# OMSI_TABLE12_v1.net
KiCad netlist of a schematic drawn in EAGLE
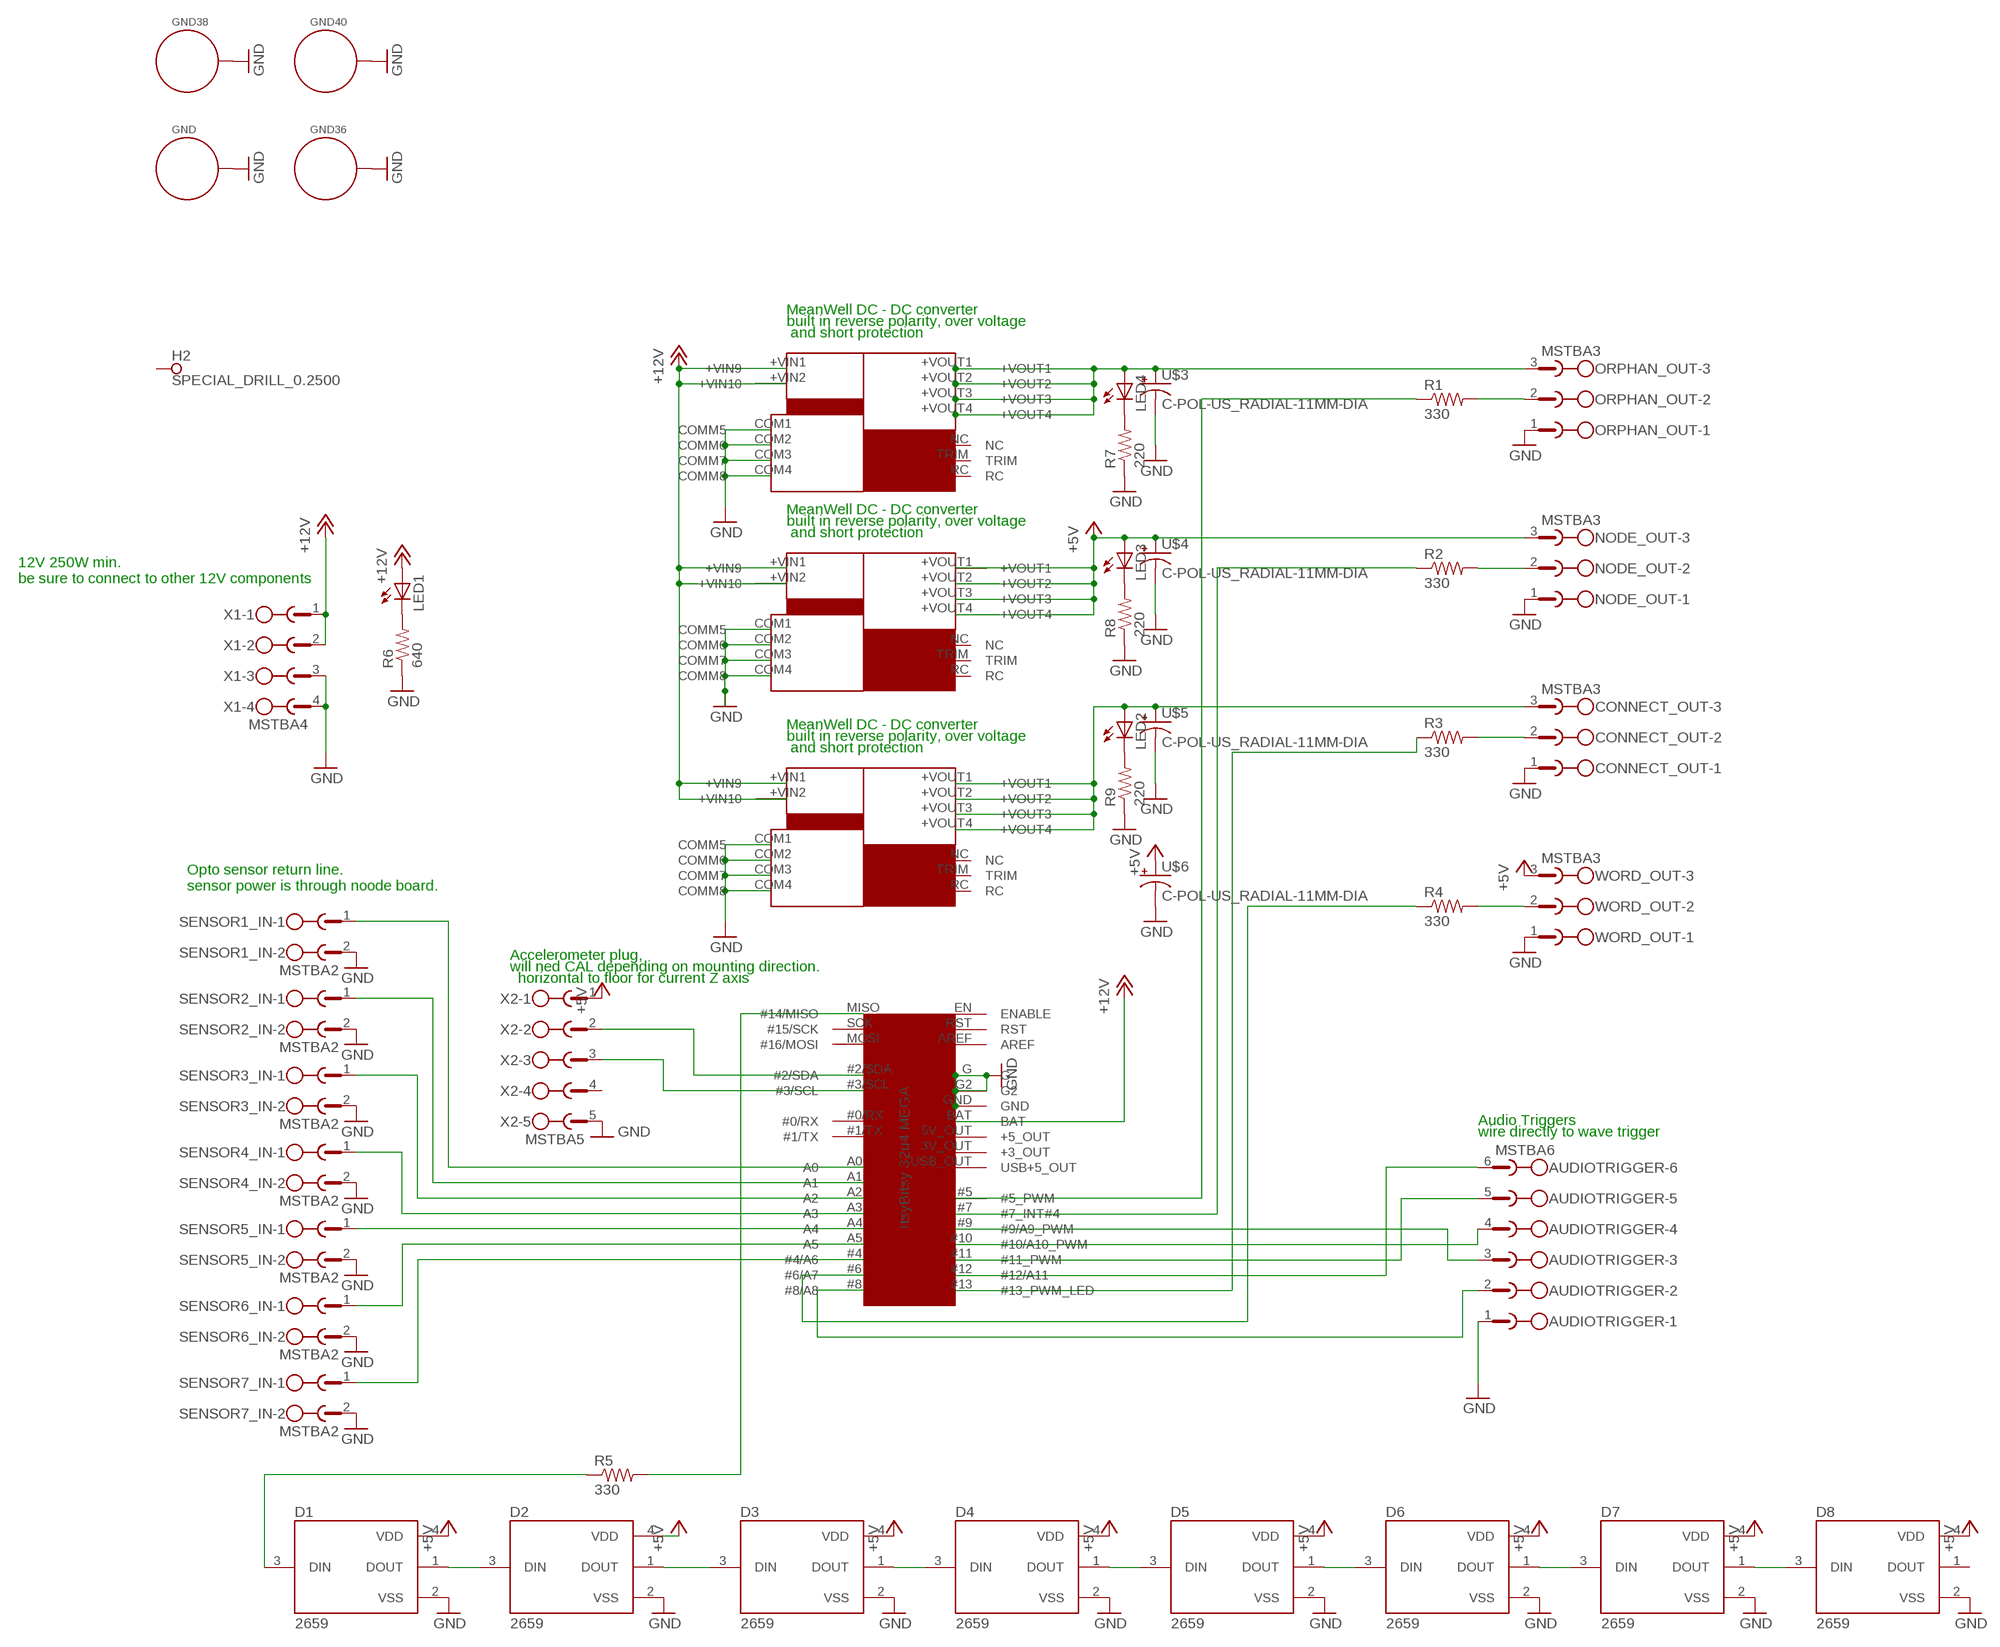
[diagram p0: schematic, sheet 1]

(export (version "E")
  (design (tool "Eeschema 10.0.6"))
  (components
    (comp (ref "AUDIOTRIGGER")
      (value "MSTBA6")
      (footprint "eagle-import:MSTBA6")
      (fields (field (name "MF") "FARNELL") (field (name "MPN") "1757284"))
      (libsource (lib "eagle-import") (part "MSTBA6"))
    )
    (comp (ref "CONNECT_OUT")
      (value "MSTBA3")
      (footprint "eagle-import:MSTBA3")
      (fields (field (name "MF") "FARNELL") (field (name "MPN") "1757255"))
      (libsource (lib "eagle-import") (part "MSTBA3"))
    )
    (comp (ref "D1")
      (value "2659")
      (footprint "eagle-import:2659")
      (fields (field (name "MF") "Adafruit Industries"))
      (libsource (lib "eagle-import") (part "2659"))
    )
    (comp (ref "D2")
      (value "2659")
      (footprint "eagle-import:2659")
      (fields (field (name "MF") "Adafruit Industries"))
      (libsource (lib "eagle-import") (part "2659"))
    )
    (comp (ref "D3")
      (value "2659")
      (footprint "eagle-import:2659")
      (fields (field (name "MF") "Adafruit Industries"))
      (libsource (lib "eagle-import") (part "2659"))
    )
    (comp (ref "D4")
      (value "2659")
      (footprint "eagle-import:2659")
      (fields (field (name "MF") "Adafruit Industries"))
      (libsource (lib "eagle-import") (part "2659"))
    )
    (comp (ref "D5")
      (value "2659")
      (footprint "eagle-import:2659")
      (fields (field (name "MF") "Adafruit Industries"))
      (libsource (lib "eagle-import") (part "2659"))
    )
    (comp (ref "D6")
      (value "2659")
      (footprint "eagle-import:2659")
      (fields (field (name "MF") "Adafruit Industries"))
      (libsource (lib "eagle-import") (part "2659"))
    )
    (comp (ref "D7")
      (value "2659")
      (footprint "eagle-import:2659")
      (fields (field (name "MF") "Adafruit Industries"))
      (libsource (lib "eagle-import") (part "2659"))
    )
    (comp (ref "D8")
      (value "2659")
      (footprint "eagle-import:2659")
      (fields (field (name "MF") "Adafruit Industries"))
      (libsource (lib "eagle-import") (part "2659"))
    )
    (comp (ref "GND")
      (value "STANDOFF_ELECTRICAL5-32")
      (footprint "eagle-import:STANDOFF_ELECTRICAL_5_32")
      (libsource (lib "eagle-import") (part "STANDOFF_ELECTRICAL5-32"))
    )
    (comp (ref "GND36")
      (value "STANDOFF_ELECTRICAL5-32")
      (footprint "eagle-import:STANDOFF_ELECTRICAL_5_32")
      (libsource (lib "eagle-import") (part "STANDOFF_ELECTRICAL5-32"))
    )
    (comp (ref "GND38")
      (value "STANDOFF_ELECTRICAL5-32")
      (footprint "eagle-import:STANDOFF_ELECTRICAL_5_32")
      (libsource (lib "eagle-import") (part "STANDOFF_ELECTRICAL5-32"))
    )
    (comp (ref "GND40")
      (value "STANDOFF_ELECTRICAL5-32")
      (footprint "eagle-import:STANDOFF_ELECTRICAL_5_32")
      (libsource (lib "eagle-import") (part "STANDOFF_ELECTRICAL5-32"))
    )
    (comp (ref "H2")
      (value "SPECIAL_DRILL_0.2500")
      (footprint "eagle-import:PAD_0.2500")
      (libsource (lib "eagle-import") (part "SPECIAL_DRILL_0.2500"))
    )
    (comp (ref "LED1")
      (value "LEDCHIPLED_1206")
      (footprint "eagle-import:CHIPLED_1206")
      (libsource (lib "eagle-import") (part "LEDCHIPLED_1206"))
    )
    (comp (ref "LED2")
      (value "LEDCHIPLED_1206")
      (footprint "eagle-import:CHIPLED_1206")
      (libsource (lib "eagle-import") (part "LEDCHIPLED_1206"))
    )
    (comp (ref "LED3")
      (value "LEDCHIPLED_1206")
      (footprint "eagle-import:CHIPLED_1206")
      (libsource (lib "eagle-import") (part "LEDCHIPLED_1206"))
    )
    (comp (ref "LED4")
      (value "LEDCHIPLED_1206")
      (footprint "eagle-import:CHIPLED_1206")
      (libsource (lib "eagle-import") (part "LEDCHIPLED_1206"))
    )
    (comp (ref "MEANWELL_NID100_1")
      (value "MEANWELL_NID100")
      (footprint "eagle-import:MEANWELL_NID100")
      (libsource (lib "eagle-import") (part "MEANWELL_NID100"))
    )
    (comp (ref "MEANWELL_NID100_2")
      (value "MEANWELL_NID100")
      (footprint "eagle-import:MEANWELL_NID100")
      (libsource (lib "eagle-import") (part "MEANWELL_NID100"))
    )
    (comp (ref "MEANWELL_NID100_3")
      (value "MEANWELL_NID100")
      (footprint "eagle-import:MEANWELL_NID100")
      (libsource (lib "eagle-import") (part "MEANWELL_NID100"))
    )
    (comp (ref "NODE_OUT")
      (value "MSTBA3")
      (footprint "eagle-import:MSTBA3")
      (fields (field (name "MF") "FARNELL") (field (name "MPN") "1757255"))
      (libsource (lib "eagle-import") (part "MSTBA3"))
    )
    (comp (ref "ORPHAN_OUT")
      (value "MSTBA3")
      (footprint "eagle-import:MSTBA3")
      (fields (field (name "MF") "FARNELL") (field (name "MPN") "1757255"))
      (libsource (lib "eagle-import") (part "MSTBA3"))
    )
    (comp (ref "R1")
      (value "330")
      (footprint "eagle-import:RESAD1176W63L850D250B")
      (libsource (lib "eagle-import") (part "R-USAXIAL-11.7MM-PITCH_"))
    )
    (comp (ref "R2")
      (value "330")
      (footprint "eagle-import:RESAD1176W63L850D250B")
      (libsource (lib "eagle-import") (part "R-USAXIAL-11.7MM-PITCH_"))
    )
    (comp (ref "R3")
      (value "330")
      (footprint "eagle-import:RESAD1176W63L850D250B")
      (libsource (lib "eagle-import") (part "R-USAXIAL-11.7MM-PITCH_"))
    )
    (comp (ref "R4")
      (value "330")
      (footprint "eagle-import:RESAD1176W63L850D250B")
      (libsource (lib "eagle-import") (part "R-USAXIAL-11.7MM-PITCH_"))
    )
    (comp (ref "R5")
      (value "330")
      (footprint "eagle-import:RESAD1176W63L850D250B")
      (libsource (lib "eagle-import") (part "R-USAXIAL-11.7MM-PITCH_"))
    )
    (comp (ref "R6")
      (value "640")
      (footprint "eagle-import:R0805")
      (libsource (lib "eagle-import") (part "adafruit_420_R-US_R0805"))
    )
    (comp (ref "R7")
      (value "220")
      (footprint "eagle-import:R0805")
      (libsource (lib "eagle-import") (part "R-US_R0805"))
    )
    (comp (ref "R8")
      (value "220")
      (footprint "eagle-import:R0805")
      (libsource (lib "eagle-import") (part "R-US_R0805"))
    )
    (comp (ref "R9")
      (value "220")
      (footprint "eagle-import:R0805")
      (libsource (lib "eagle-import") (part "R-US_R0805"))
    )
    (comp (ref "SENSOR1_IN")
      (value "MSTBA2")
      (footprint "eagle-import:MSTBA2")
      (fields (field (name "MF") "FARNELL") (field (name "MPN") "1757242"))
      (libsource (lib "eagle-import") (part "MSTBA2"))
    )
    (comp (ref "SENSOR2_IN")
      (value "MSTBA2")
      (footprint "eagle-import:MSTBA2")
      (fields (field (name "MF") "FARNELL") (field (name "MPN") "1757242"))
      (libsource (lib "eagle-import") (part "MSTBA2"))
    )
    (comp (ref "SENSOR3_IN")
      (value "MSTBA2")
      (footprint "eagle-import:MSTBA2")
      (fields (field (name "MF") "FARNELL") (field (name "MPN") "1757242"))
      (libsource (lib "eagle-import") (part "MSTBA2"))
    )
    (comp (ref "SENSOR4_IN")
      (value "MSTBA2")
      (footprint "eagle-import:MSTBA2")
      (fields (field (name "MF") "FARNELL") (field (name "MPN") "1757242"))
      (libsource (lib "eagle-import") (part "MSTBA2"))
    )
    (comp (ref "SENSOR5_IN")
      (value "MSTBA2")
      (footprint "eagle-import:MSTBA2")
      (fields (field (name "MF") "FARNELL") (field (name "MPN") "1757242"))
      (libsource (lib "eagle-import") (part "MSTBA2"))
    )
    (comp (ref "SENSOR6_IN")
      (value "MSTBA2")
      (footprint "eagle-import:MSTBA2")
      (fields (field (name "MF") "FARNELL") (field (name "MPN") "1757242"))
      (libsource (lib "eagle-import") (part "MSTBA2"))
    )
    (comp (ref "SENSOR7_IN")
      (value "MSTBA2")
      (footprint "eagle-import:MSTBA2")
      (fields (field (name "MF") "FARNELL") (field (name "MPN") "1757242"))
      (libsource (lib "eagle-import") (part "MSTBA2"))
    )
    (comp (ref "U$1")
      (value "ITSYBITSY_32U4")
      (footprint "eagle-import:ITSYBITSY_32U4")
      (libsource (lib "eagle-import") (part "ITSYBITSY_32U4"))
    )
    (comp (ref "U$3")
      (value "C-POL-US_RADIAL-11MM-DIA")
      (footprint "eagle-import:CAPPRD508W65D1000H1100B")
      (libsource (lib "eagle-import") (part "C-POL-USRADIAL-11MM-DIA_"))
    )
    (comp (ref "U$4")
      (value "C-POL-US_RADIAL-11MM-DIA")
      (footprint "eagle-import:CAPPRD508W65D1000H1100B")
      (libsource (lib "eagle-import") (part "C-POL-USRADIAL-11MM-DIA_"))
    )
    (comp (ref "U$5")
      (value "C-POL-US_RADIAL-11MM-DIA")
      (footprint "eagle-import:CAPPRD508W65D1000H1100B")
      (libsource (lib "eagle-import") (part "C-POL-USRADIAL-11MM-DIA_"))
    )
    (comp (ref "U$6")
      (value "C-POL-US_RADIAL-11MM-DIA")
      (footprint "eagle-import:CAPPRD508W65D1000H1100B")
      (libsource (lib "eagle-import") (part "C-POL-USRADIAL-11MM-DIA_"))
    )
    (comp (ref "WORD_OUT")
      (value "MSTBA3")
      (footprint "eagle-import:MSTBA3")
      (fields (field (name "MF") "FARNELL") (field (name "MPN") "1757255"))
      (libsource (lib "eagle-import") (part "MSTBA3"))
    )
    (comp (ref "X1")
      (value "MSTBA4")
      (footprint "eagle-import:MSTBA4")
      (fields (field (name "MF") "FARNELL") (field (name "MPN") "1757268"))
      (libsource (lib "eagle-import") (part "MSTBA4"))
    )
    (comp (ref "X2")
      (value "MSTBA5")
      (footprint "eagle-import:MSTBA5")
      (fields (field (name "MPN") "1757271"))
      (libsource (lib "eagle-import") (part "MSTBA5"))
    )
  )
  (nets
    (net (code "1") (name "+5V") (class "Default")
      (node (ref "D1") (pin "4") (pinfunction "VDD_4") (pintype "power_in"))
      (node (ref "D2") (pin "4") (pinfunction "VDD_4") (pintype "power_in"))
      (node (ref "D3") (pin "4") (pinfunction "VDD_4") (pintype "power_in"))
      (node (ref "D4") (pin "4") (pinfunction "VDD_4") (pintype "power_in"))
      (node (ref "D5") (pin "4") (pinfunction "VDD_4") (pintype "power_in"))
      (node (ref "D6") (pin "4") (pinfunction "VDD_4") (pintype "power_in"))
      (node (ref "D7") (pin "4") (pinfunction "VDD_4") (pintype "power_in"))
      (node (ref "D8") (pin "4") (pinfunction "VDD_4") (pintype "power_in"))
      (node (ref "LED3") (pin "A") (pinfunction "A_A") (pintype "passive"))
      (node (ref "MEANWELL_NID100_3") (pin "+VOUT1") (pinfunction "+VOUT1_+VOUT1") (pintype "power_in"))
      (node (ref "MEANWELL_NID100_3") (pin "+VOUT2") (pinfunction "+VOUT2_+VOUT2") (pintype "power_in"))
      (node (ref "MEANWELL_NID100_3") (pin "+VOUT3") (pinfunction "+VOUT3_+VOUT3") (pintype "power_in"))
      (node (ref "MEANWELL_NID100_3") (pin "+VOUT4") (pinfunction "+VOUT4_+VOUT4") (pintype "power_in"))
      (node (ref "NODE_OUT") (pin "3") (pinfunction "1_3") (pintype "passive"))
      (node (ref "U$4") (pin "1") (pinfunction "+_1") (pintype "passive"))
      (node (ref "U$6") (pin "1") (pinfunction "+_1") (pintype "passive"))
      (node (ref "WORD_OUT") (pin "3") (pinfunction "1_3") (pintype "passive"))
      (node (ref "X2") (pin "1") (pinfunction "1_1") (pintype "passive"))
    )
    (net (code "2") (name "+12V") (class "Default")
      (node (ref "LED1") (pin "A") (pinfunction "A_A") (pintype "passive"))
      (node (ref "MEANWELL_NID100_1") (pin "+VIN1") (pinfunction "+VIN9_+VIN1") (pintype "power_in"))
      (node (ref "MEANWELL_NID100_1") (pin "+VIN2") (pinfunction "+VIN10_+VIN2") (pintype "power_in"))
      (node (ref "MEANWELL_NID100_2") (pin "+VIN1") (pinfunction "+VIN9_+VIN1") (pintype "power_in"))
      (node (ref "MEANWELL_NID100_2") (pin "+VIN2") (pinfunction "+VIN10_+VIN2") (pintype "power_in"))
      (node (ref "MEANWELL_NID100_3") (pin "+VIN1") (pinfunction "+VIN9_+VIN1") (pintype "power_in"))
      (node (ref "MEANWELL_NID100_3") (pin "+VIN2") (pinfunction "+VIN10_+VIN2") (pintype "power_in"))
      (node (ref "U$1") (pin "BAT") (pinfunction "BAT_BAT") (pintype "power_in"))
      (node (ref "X1") (pin "1") (pinfunction "1_1") (pintype "passive"))
      (node (ref "X1") (pin "2") (pinfunction "1_2") (pintype "passive"))
    )
    (net (code "3") (name "/+3_OUT") (class "Default")
      (node (ref "U$1") (pin "3V_OUT") (pinfunction "+3_OUT_3V_OUT") (pintype "power_in"))
    )
    (net (code "4") (name "/+5_OUT") (class "Default")
      (node (ref "U$1") (pin "5V_OUT") (pinfunction "+5_OUT_5V_OUT") (pintype "power_in"))
    )
    (net (code "5") (name "/AREF") (class "Default")
      (node (ref "U$1") (pin "AREF") (pinfunction "AREF_AREF") (pintype "power_in"))
    )
    (net (code "6") (name "/RST") (class "Default")
      (node (ref "U$1") (pin "RST") (pinfunction "RST_RST") (pintype "power_in"))
    )
    (net (code "7") (name "/USB+5_OUT") (class "Default")
      (node (ref "U$1") (pin "USB_OUT") (pinfunction "USB+5_OUT_USB_OUT") (pintype "power_in"))
    )
    (net (code "8") (name "GND") (class "Default")
      (node (ref "AUDIOTRIGGER") (pin "1") (pinfunction "1_1") (pintype "passive"))
      (node (ref "CONNECT_OUT") (pin "1") (pinfunction "1_1") (pintype "passive"))
      (node (ref "D1") (pin "2") (pinfunction "VSS_2") (pintype "power_in"))
      (node (ref "D2") (pin "2") (pinfunction "VSS_2") (pintype "power_in"))
      (node (ref "D3") (pin "2") (pinfunction "VSS_2") (pintype "power_in"))
      (node (ref "D4") (pin "2") (pinfunction "VSS_2") (pintype "power_in"))
      (node (ref "D5") (pin "2") (pinfunction "VSS_2") (pintype "power_in"))
      (node (ref "D6") (pin "2") (pinfunction "VSS_2") (pintype "power_in"))
      (node (ref "D7") (pin "2") (pinfunction "VSS_2") (pintype "power_in"))
      (node (ref "D8") (pin "2") (pinfunction "VSS_2") (pintype "power_in"))
      (node (ref "GND") (pin "P1") (pinfunction "P$1_P1") (pintype "bidirectional"))
      (node (ref "GND36") (pin "P1") (pinfunction "P$1_P1") (pintype "bidirectional"))
      (node (ref "GND38") (pin "P1") (pinfunction "P$1_P1") (pintype "bidirectional"))
      (node (ref "GND40") (pin "P1") (pinfunction "P$1_P1") (pintype "bidirectional"))
      (node (ref "MEANWELL_NID100_1") (pin "COM1") (pinfunction "COMM5_COM1") (pintype "power_in"))
      (node (ref "MEANWELL_NID100_1") (pin "COM2") (pinfunction "COMM6_COM2") (pintype "power_in"))
      (node (ref "MEANWELL_NID100_1") (pin "COM3") (pinfunction "COMM7_COM3") (pintype "power_in"))
      (node (ref "MEANWELL_NID100_1") (pin "COM4") (pinfunction "COMM8_COM4") (pintype "power_in"))
      (node (ref "MEANWELL_NID100_2") (pin "COM1") (pinfunction "COMM5_COM1") (pintype "power_in"))
      (node (ref "MEANWELL_NID100_2") (pin "COM2") (pinfunction "COMM6_COM2") (pintype "power_in"))
      (node (ref "MEANWELL_NID100_2") (pin "COM3") (pinfunction "COMM7_COM3") (pintype "power_in"))
      (node (ref "MEANWELL_NID100_2") (pin "COM4") (pinfunction "COMM8_COM4") (pintype "power_in"))
      (node (ref "MEANWELL_NID100_3") (pin "COM1") (pinfunction "COMM5_COM1") (pintype "power_in"))
      (node (ref "MEANWELL_NID100_3") (pin "COM2") (pinfunction "COMM6_COM2") (pintype "power_in"))
      (node (ref "MEANWELL_NID100_3") (pin "COM3") (pinfunction "COMM7_COM3") (pintype "power_in"))
      (node (ref "MEANWELL_NID100_3") (pin "COM4") (pinfunction "COMM8_COM4") (pintype "power_in"))
      (node (ref "NODE_OUT") (pin "1") (pinfunction "1_1") (pintype "passive"))
      (node (ref "ORPHAN_OUT") (pin "1") (pinfunction "1_1") (pintype "passive"))
      (node (ref "R6") (pin "1") (pinfunction "1_1") (pintype "passive"))
      (node (ref "R7") (pin "1") (pinfunction "1_1") (pintype "passive"))
      (node (ref "R8") (pin "1") (pinfunction "1_1") (pintype "passive"))
      (node (ref "R9") (pin "1") (pinfunction "1_1") (pintype "passive"))
      (node (ref "SENSOR1_IN") (pin "2") (pinfunction "1_2") (pintype "passive"))
      (node (ref "SENSOR2_IN") (pin "2") (pinfunction "1_2") (pintype "passive"))
      (node (ref "SENSOR3_IN") (pin "2") (pinfunction "1_2") (pintype "passive"))
      (node (ref "SENSOR4_IN") (pin "2") (pinfunction "1_2") (pintype "passive"))
      (node (ref "SENSOR5_IN") (pin "2") (pinfunction "1_2") (pintype "passive"))
      (node (ref "SENSOR6_IN") (pin "2") (pinfunction "1_2") (pintype "passive"))
      (node (ref "SENSOR7_IN") (pin "2") (pinfunction "1_2") (pintype "passive"))
      (node (ref "U$1") (pin "G") (pinfunction "G_G") (pintype "power_in"))
      (node (ref "U$1") (pin "G2") (pinfunction "G2_G2") (pintype "power_in"))
      (node (ref "U$1") (pin "GND") (pinfunction "GND_GND") (pintype "power_in"))
      (node (ref "U$3") (pin "2") (pinfunction "-_2") (pintype "passive"))
      (node (ref "U$4") (pin "2") (pinfunction "-_2") (pintype "passive"))
      (node (ref "U$5") (pin "2") (pinfunction "-_2") (pintype "passive"))
      (node (ref "U$6") (pin "2") (pinfunction "-_2") (pintype "passive"))
      (node (ref "WORD_OUT") (pin "1") (pinfunction "1_1") (pintype "passive"))
      (node (ref "X1") (pin "3") (pinfunction "1_3") (pintype "passive"))
      (node (ref "X1") (pin "4") (pinfunction "1_4") (pintype "passive"))
      (node (ref "X2") (pin "5") (pinfunction "1_5") (pintype "passive"))
    )
    (net (code "9") (name "Net-(AUDIOTRIGGERB-1)") (class "Default")
      (node (ref "AUDIOTRIGGER") (pin "2") (pinfunction "1_2") (pintype "passive"))
      (node (ref "U$1") (pin "#8") (pinfunction "#8/A8_#8") (pintype "bidirectional"))
    )
    (net (code "10") (name "Net-(AUDIOTRIGGERC-1)") (class "Default")
      (node (ref "AUDIOTRIGGER") (pin "3") (pinfunction "1_3") (pintype "passive"))
      (node (ref "U$1") (pin "#9") (pinfunction "#9/A9_PWM_#9") (pintype "bidirectional"))
    )
    (net (code "11") (name "Net-(AUDIOTRIGGERD-1)") (class "Default")
      (node (ref "AUDIOTRIGGER") (pin "4") (pinfunction "1_4") (pintype "passive"))
      (node (ref "U$1") (pin "#10") (pinfunction "#10/A10_PWM_#10") (pintype "bidirectional"))
    )
    (net (code "12") (name "Net-(AUDIOTRIGGERE-1)") (class "Default")
      (node (ref "AUDIOTRIGGER") (pin "5") (pinfunction "1_5") (pintype "passive"))
      (node (ref "U$1") (pin "#11") (pinfunction "#11_PWM_#11") (pintype "bidirectional"))
    )
    (net (code "13") (name "Net-(AUDIOTRIGGERF-1)") (class "Default")
      (node (ref "AUDIOTRIGGER") (pin "6") (pinfunction "1_6") (pintype "passive"))
      (node (ref "U$1") (pin "#12") (pinfunction "#12/A11_#12") (pintype "bidirectional"))
    )
    (net (code "14") (name "Net-(CONNECT_OUTB-1)") (class "Default")
      (node (ref "CONNECT_OUT") (pin "2") (pinfunction "1_2") (pintype "passive"))
      (node (ref "R3") (pin "2") (pinfunction "2_2") (pintype "passive"))
    )
    (net (code "15") (name "Net-(CONNECT_OUTC-1)") (class "Default")
      (node (ref "CONNECT_OUT") (pin "3") (pinfunction "1_3") (pintype "passive"))
      (node (ref "LED2") (pin "A") (pinfunction "A_A") (pintype "passive"))
      (node (ref "MEANWELL_NID100_1") (pin "+VOUT1") (pinfunction "+VOUT1_+VOUT1") (pintype "power_in"))
      (node (ref "MEANWELL_NID100_1") (pin "+VOUT2") (pinfunction "+VOUT2_+VOUT2") (pintype "power_in"))
      (node (ref "MEANWELL_NID100_1") (pin "+VOUT3") (pinfunction "+VOUT3_+VOUT3") (pintype "power_in"))
      (node (ref "MEANWELL_NID100_1") (pin "+VOUT4") (pinfunction "+VOUT4_+VOUT4") (pintype "power_in"))
      (node (ref "U$5") (pin "1") (pinfunction "+_1") (pintype "passive"))
    )
    (net (code "16") (name "Net-(D1-DIN)") (class "Default")
      (node (ref "D1") (pin "3") (pinfunction "DIN_3") (pintype "input"))
      (node (ref "R5") (pin "1") (pinfunction "1_1") (pintype "passive"))
    )
    (net (code "17") (name "Net-(D1-DOUT)") (class "Default")
      (node (ref "D1") (pin "1") (pinfunction "DOUT_1") (pintype "output"))
      (node (ref "D2") (pin "3") (pinfunction "DIN_3") (pintype "input"))
    )
    (net (code "18") (name "Net-(D2-DOUT)") (class "Default")
      (node (ref "D2") (pin "1") (pinfunction "DOUT_1") (pintype "output"))
      (node (ref "D3") (pin "3") (pinfunction "DIN_3") (pintype "input"))
    )
    (net (code "19") (name "Net-(D3-DOUT)") (class "Default")
      (node (ref "D3") (pin "1") (pinfunction "DOUT_1") (pintype "output"))
      (node (ref "D4") (pin "3") (pinfunction "DIN_3") (pintype "input"))
    )
    (net (code "20") (name "Net-(D4-DOUT)") (class "Default")
      (node (ref "D4") (pin "1") (pinfunction "DOUT_1") (pintype "output"))
      (node (ref "D5") (pin "3") (pinfunction "DIN_3") (pintype "input"))
    )
    (net (code "21") (name "Net-(D5-DOUT)") (class "Default")
      (node (ref "D5") (pin "1") (pinfunction "DOUT_1") (pintype "output"))
      (node (ref "D6") (pin "3") (pinfunction "DIN_3") (pintype "input"))
    )
    (net (code "22") (name "Net-(D6-DOUT)") (class "Default")
      (node (ref "D6") (pin "1") (pinfunction "DOUT_1") (pintype "output"))
      (node (ref "D7") (pin "3") (pinfunction "DIN_3") (pintype "input"))
    )
    (net (code "23") (name "Net-(D7-DOUT)") (class "Default")
      (node (ref "D7") (pin "1") (pinfunction "DOUT_1") (pintype "output"))
      (node (ref "D8") (pin "3") (pinfunction "DIN_3") (pintype "input"))
    )
    (net (code "24") (name "Net-(LED1-PadC)") (class "Default")
      (node (ref "LED1") (pin "C") (pinfunction "C_C") (pintype "passive"))
      (node (ref "R6") (pin "2") (pinfunction "2_2") (pintype "passive"))
    )
    (net (code "25") (name "Net-(LED2-PadC)") (class "Default")
      (node (ref "LED2") (pin "C") (pinfunction "C_C") (pintype "passive"))
      (node (ref "R9") (pin "2") (pinfunction "2_2") (pintype "passive"))
    )
    (net (code "26") (name "Net-(LED3-PadC)") (class "Default")
      (node (ref "LED3") (pin "C") (pinfunction "C_C") (pintype "passive"))
      (node (ref "R8") (pin "2") (pinfunction "2_2") (pintype "passive"))
    )
    (net (code "27") (name "Net-(LED4-PadC)") (class "Default")
      (node (ref "LED4") (pin "C") (pinfunction "C_C") (pintype "passive"))
      (node (ref "R7") (pin "2") (pinfunction "2_2") (pintype "passive"))
    )
    (net (code "28") (name "Net-(NODE_OUTB-1)") (class "Default")
      (node (ref "NODE_OUT") (pin "2") (pinfunction "1_2") (pintype "passive"))
      (node (ref "R2") (pin "2") (pinfunction "2_2") (pintype "passive"))
    )
    (net (code "29") (name "Net-(ORPHAN_OUTB-1)") (class "Default")
      (node (ref "ORPHAN_OUT") (pin "2") (pinfunction "1_2") (pintype "passive"))
      (node (ref "R1") (pin "2") (pinfunction "2_2") (pintype "passive"))
    )
    (net (code "30") (name "Net-(ORPHAN_OUTC-1)") (class "Default")
      (node (ref "LED4") (pin "A") (pinfunction "A_A") (pintype "passive"))
      (node (ref "MEANWELL_NID100_2") (pin "+VOUT1") (pinfunction "+VOUT1_+VOUT1") (pintype "power_in"))
      (node (ref "MEANWELL_NID100_2") (pin "+VOUT2") (pinfunction "+VOUT2_+VOUT2") (pintype "power_in"))
      (node (ref "MEANWELL_NID100_2") (pin "+VOUT3") (pinfunction "+VOUT3_+VOUT3") (pintype "power_in"))
      (node (ref "MEANWELL_NID100_2") (pin "+VOUT4") (pinfunction "+VOUT4_+VOUT4") (pintype "power_in"))
      (node (ref "ORPHAN_OUT") (pin "3") (pinfunction "1_3") (pintype "passive"))
      (node (ref "U$3") (pin "1") (pinfunction "+_1") (pintype "passive"))
    )
    (net (code "31") (name "Net-(SENSOR1_IN-Pad1)") (class "Default")
      (node (ref "SENSOR1_IN") (pin "1") (pinfunction "1_1") (pintype "passive"))
      (node (ref "U$1") (pin "A0") (pinfunction "A0_A0") (pintype "bidirectional"))
    )
    (net (code "32") (name "Net-(SENSOR2_IN-Pad1)") (class "Default")
      (node (ref "SENSOR2_IN") (pin "1") (pinfunction "1_1") (pintype "passive"))
      (node (ref "U$1") (pin "A1") (pinfunction "A1_A1") (pintype "bidirectional"))
    )
    (net (code "33") (name "Net-(SENSOR3_IN-Pad1)") (class "Default")
      (node (ref "SENSOR3_IN") (pin "1") (pinfunction "1_1") (pintype "passive"))
      (node (ref "U$1") (pin "A2") (pinfunction "A2_A2") (pintype "bidirectional"))
    )
    (net (code "34") (name "Net-(SENSOR4_IN-Pad1)") (class "Default")
      (node (ref "SENSOR4_IN") (pin "1") (pinfunction "1_1") (pintype "passive"))
      (node (ref "U$1") (pin "A3") (pinfunction "A3_A3") (pintype "bidirectional"))
    )
    (net (code "35") (name "Net-(SENSOR5_IN-Pad1)") (class "Default")
      (node (ref "SENSOR5_IN") (pin "1") (pinfunction "1_1") (pintype "passive"))
      (node (ref "U$1") (pin "A4") (pinfunction "A4_A4") (pintype "bidirectional"))
    )
    (net (code "36") (name "Net-(SENSOR6_IN-Pad1)") (class "Default")
      (node (ref "SENSOR6_IN") (pin "1") (pinfunction "1_1") (pintype "passive"))
      (node (ref "U$1") (pin "A5") (pinfunction "A5_A5") (pintype "bidirectional"))
    )
    (net (code "37") (name "Net-(U$1-#4{slash}A6)") (class "Default")
      (node (ref "SENSOR7_IN") (pin "1") (pinfunction "1_1") (pintype "passive"))
      (node (ref "U$1") (pin "#4") (pinfunction "#4/A6_#4") (pintype "input"))
    )
    (net (code "38") (name "Net-(U$1-#5_PWM)") (class "Default")
      (node (ref "R1") (pin "1") (pinfunction "1_1") (pintype "passive"))
      (node (ref "U$1") (pin "#5") (pinfunction "#5_PWM_#5") (pintype "bidirectional"))
    )
    (net (code "39") (name "Net-(U$1-#6{slash}A7)") (class "Default")
      (node (ref "R4") (pin "1") (pinfunction "1_1") (pintype "passive"))
      (node (ref "U$1") (pin "#6") (pinfunction "#6/A7_#6") (pintype "bidirectional"))
    )
    (net (code "40") (name "Net-(U$1-#7_INT#4)") (class "Default")
      (node (ref "R2") (pin "1") (pinfunction "1_1") (pintype "passive"))
      (node (ref "U$1") (pin "#7") (pinfunction "#7_INT#4_#7") (pintype "bidirectional"))
    )
    (net (code "41") (name "Net-(U$1-#13_PWM_LED)") (class "Default")
      (node (ref "R3") (pin "1") (pinfunction "1_1") (pintype "passive"))
      (node (ref "U$1") (pin "#13") (pinfunction "#13_PWM_LED_#13") (pintype "bidirectional"))
    )
    (net (code "42") (name "Net-(U$1-#14{slash}MISO)") (class "Default")
      (node (ref "R5") (pin "2") (pinfunction "2_2") (pintype "passive"))
      (node (ref "U$1") (pin "MISO") (pinfunction "#14/MISO_MISO") (pintype "bidirectional"))
    )
    (net (code "43") (name "Net-(WORD_OUTB-1)") (class "Default")
      (node (ref "R4") (pin "2") (pinfunction "2_2") (pintype "passive"))
      (node (ref "WORD_OUT") (pin "2") (pinfunction "1_2") (pintype "passive"))
    )
    (net (code "44") (name "Net-(X2B-1)") (class "Default")
      (node (ref "U$1") (pin "#2/SDA") (pinfunction "#2/SDA_#2/SDA") (pintype "bidirectional"))
      (node (ref "X2") (pin "2") (pinfunction "1_2") (pintype "passive"))
    )
    (net (code "45") (name "Net-(X2C-1)") (class "Default")
      (node (ref "U$1") (pin "#3/SCL") (pinfunction "#3/SCL_#3/SCL") (pintype "bidirectional"))
      (node (ref "X2") (pin "3") (pinfunction "1_3") (pintype "passive"))
    )
    (net (code "46") (name "unconnected-(D8-DOUT-Pad1)") (class "Default")
      (node (ref "D8") (pin "1") (pinfunction "DOUT_1") (pintype "output"))
    )
    (net (code "47") (name "unconnected-(H2-Pad1)") (class "Default")
      (node (ref "H2") (pin "1") (pinfunction "1_1") (pintype "passive"))
    )
    (net (code "48") (name "unconnected-(MEANWELL_NID100_1-PadNC)") (class "Default")
      (node (ref "MEANWELL_NID100_1") (pin "NC") (pinfunction "NC_NC") (pintype "no_connect"))
    )
    (net (code "49") (name "unconnected-(MEANWELL_NID100_1-PadRC)") (class "Default")
      (node (ref "MEANWELL_NID100_1") (pin "RC") (pinfunction "RC_RC") (pintype "no_connect"))
    )
    (net (code "50") (name "unconnected-(MEANWELL_NID100_1-PadTRIM)") (class "Default")
      (node (ref "MEANWELL_NID100_1") (pin "TRIM") (pinfunction "TRIM_TRIM") (pintype "no_connect"))
    )
    (net (code "51") (name "unconnected-(MEANWELL_NID100_2-PadNC)") (class "Default")
      (node (ref "MEANWELL_NID100_2") (pin "NC") (pinfunction "NC_NC") (pintype "no_connect"))
    )
    (net (code "52") (name "unconnected-(MEANWELL_NID100_2-PadRC)") (class "Default")
      (node (ref "MEANWELL_NID100_2") (pin "RC") (pinfunction "RC_RC") (pintype "no_connect"))
    )
    (net (code "53") (name "unconnected-(MEANWELL_NID100_2-PadTRIM)") (class "Default")
      (node (ref "MEANWELL_NID100_2") (pin "TRIM") (pinfunction "TRIM_TRIM") (pintype "no_connect"))
    )
    (net (code "54") (name "unconnected-(MEANWELL_NID100_3-PadNC)") (class "Default")
      (node (ref "MEANWELL_NID100_3") (pin "NC") (pinfunction "NC_NC") (pintype "no_connect"))
    )
    (net (code "55") (name "unconnected-(MEANWELL_NID100_3-PadRC)") (class "Default")
      (node (ref "MEANWELL_NID100_3") (pin "RC") (pinfunction "RC_RC") (pintype "no_connect"))
    )
    (net (code "56") (name "unconnected-(MEANWELL_NID100_3-PadTRIM)") (class "Default")
      (node (ref "MEANWELL_NID100_3") (pin "TRIM") (pinfunction "TRIM_TRIM") (pintype "no_connect"))
    )
    (net (code "57") (name "unconnected-(U$1-#15{slash}SCK-PadSCK)") (class "Default")
      (node (ref "U$1") (pin "SCK") (pinfunction "#15/SCK_SCK") (pintype "bidirectional"))
    )
    (net (code "58") (name "unconnected-(U$1-#16{slash}MOSI-PadMOSI)") (class "Default")
      (node (ref "U$1") (pin "MOSI") (pinfunction "#16/MOSI_MOSI") (pintype "bidirectional"))
    )
    (net (code "59") (name "unconnected-(U$1-ENABLE-PadEN)") (class "Default")
      (node (ref "U$1") (pin "EN") (pinfunction "ENABLE_EN") (pintype "input"))
    )
    (net (code "60") (name "unconnected-(U$1-Pad#0{slash}RX)") (class "Default")
      (node (ref "U$1") (pin "#0/RX") (pinfunction "#0/RX_#0/RX") (pintype "bidirectional"))
    )
    (net (code "61") (name "unconnected-(U$1-Pad#1{slash}TX)") (class "Default")
      (node (ref "U$1") (pin "#1/TX") (pinfunction "#1/TX_#1/TX") (pintype "bidirectional"))
    )
    (net (code "62") (name "unconnected-(X2D-1-Pad4)") (class "Default")
      (node (ref "X2") (pin "4") (pinfunction "1_4") (pintype "passive"))
    )
  )
)
